# POWR0004.net
KiCad netlist of a schematic drawn in Altium Designer
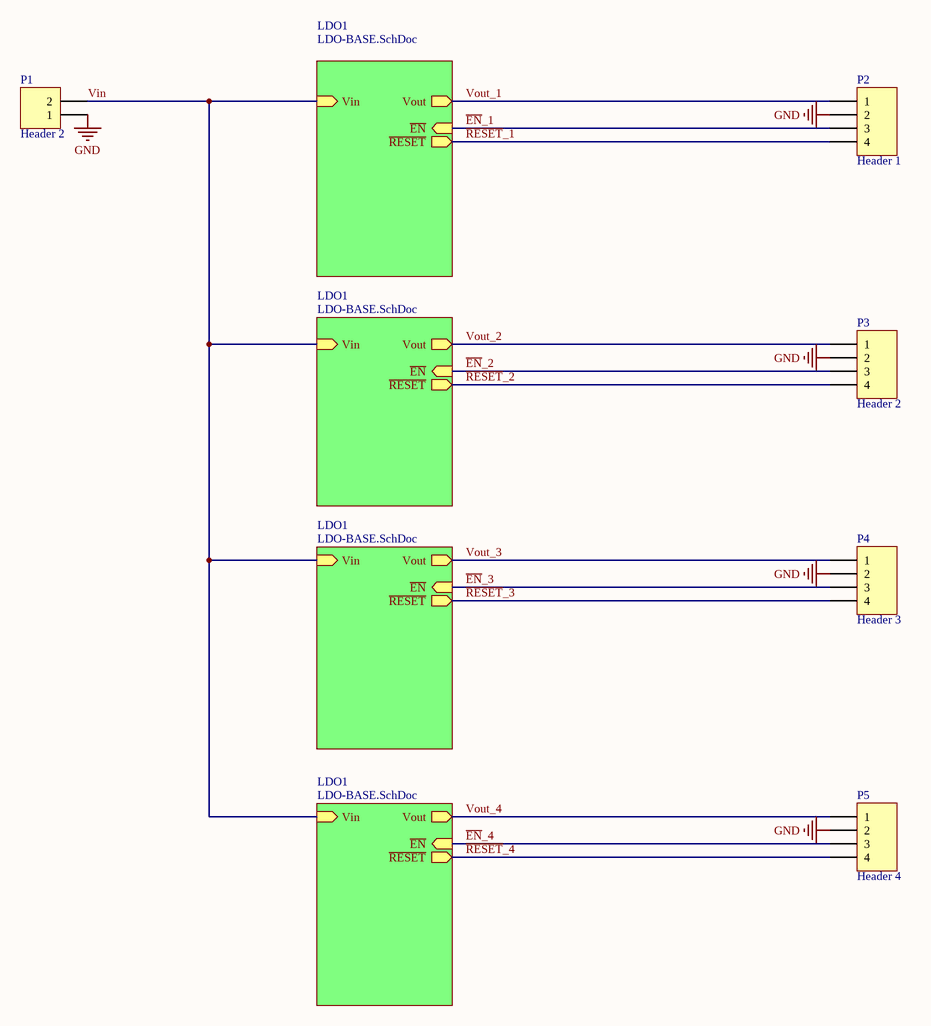
[diagram p0: POWR0004.SchDoc]

(export (version "E")
  (design (tool "Eeschema 10.0.6"))
  (components
    (comp (ref "P1")
      (value "Header 2")
      (footprint "HDR1X2")
      (description "Header, 2-Pin")
      (fields (field (name "PUBLISHER") "Altium Limited"))
      (libsource (lib "Miscellaneous Connectors") (part "Header 2"))
    )
    (comp (ref "P2")
      (value "Header 1")
      (footprint "HDR1X4")
      (description "Header, 4-Pin")
      (fields (field (name "PUBLISHER") "Altium Limited"))
      (libsource (lib "Miscellaneous Connectors") (part "Header 4"))
    )
    (comp (ref "P3")
      (value "Header 2")
      (footprint "HDR1X4")
      (description "Header, 4-Pin")
      (fields (field (name "PUBLISHER") "Altium Limited"))
      (libsource (lib "Miscellaneous Connectors") (part "Header 4"))
    )
    (comp (ref "P4")
      (value "Header 3")
      (footprint "HDR1X4")
      (description "Header, 4-Pin")
      (fields (field (name "PUBLISHER") "Altium Limited"))
      (libsource (lib "Miscellaneous Connectors") (part "Header 4"))
    )
    (comp (ref "P5")
      (value "Header 4")
      (footprint "HDR1X4")
      (description "Header, 4-Pin")
      (fields (field (name "PUBLISHER") "Altium Limited"))
      (libsource (lib "Miscellaneous Connectors") (part "Header 4"))
    )
  )
  (nets
    (net (code "1") (name "/Vin") (class "Default")
      (node (ref "P1") (pin "2") (pinfunction "2_2") (pintype "passive"))
    )
    (net (code "2") (name "/Vout_1") (class "Default")
      (node (ref "P2") (pin "1") (pinfunction "1_1") (pintype "passive"))
    )
    (net (code "3") (name "/Vout_2") (class "Default")
      (node (ref "P3") (pin "1") (pinfunction "1_1") (pintype "passive"))
    )
    (net (code "4") (name "/Vout_3") (class "Default")
      (node (ref "P4") (pin "1") (pinfunction "1_1") (pintype "passive"))
    )
    (net (code "5") (name "/Vout_4") (class "Default")
      (node (ref "P5") (pin "1") (pinfunction "1_1") (pintype "passive"))
    )
    (net (code "6") (name "/~{EN}_1") (class "Default")
      (node (ref "P2") (pin "3") (pinfunction "3_3") (pintype "passive"))
    )
    (net (code "7") (name "/~{EN}_2") (class "Default")
      (node (ref "P3") (pin "3") (pinfunction "3_3") (pintype "passive"))
    )
    (net (code "8") (name "/~{EN}_3") (class "Default")
      (node (ref "P4") (pin "3") (pinfunction "3_3") (pintype "passive"))
    )
    (net (code "9") (name "/~{EN}_4") (class "Default")
      (node (ref "P5") (pin "3") (pinfunction "3_3") (pintype "passive"))
    )
    (net (code "10") (name "/~{RESET}_1") (class "Default")
      (node (ref "P2") (pin "4") (pinfunction "4_4") (pintype "passive"))
    )
    (net (code "11") (name "/~{RESET}_2") (class "Default")
      (node (ref "P3") (pin "4") (pinfunction "4_4") (pintype "passive"))
    )
    (net (code "12") (name "/~{RESET}_3") (class "Default")
      (node (ref "P4") (pin "4") (pinfunction "4_4") (pintype "passive"))
    )
    (net (code "13") (name "/~{RESET}_4") (class "Default")
      (node (ref "P5") (pin "4") (pinfunction "4_4") (pintype "passive"))
    )
    (net (code "14") (name "GND") (class "Default")
      (node (ref "P1") (pin "1") (pinfunction "1_1") (pintype "passive"))
      (node (ref "P2") (pin "2") (pinfunction "2_2") (pintype "passive"))
      (node (ref "P3") (pin "2") (pinfunction "2_2") (pintype "passive"))
      (node (ref "P4") (pin "2") (pinfunction "2_2") (pintype "passive"))
      (node (ref "P5") (pin "2") (pinfunction "2_2") (pintype "passive"))
    )
  )
)
